# interface.net
KiCad netlist of a schematic drawn in Altium Designer
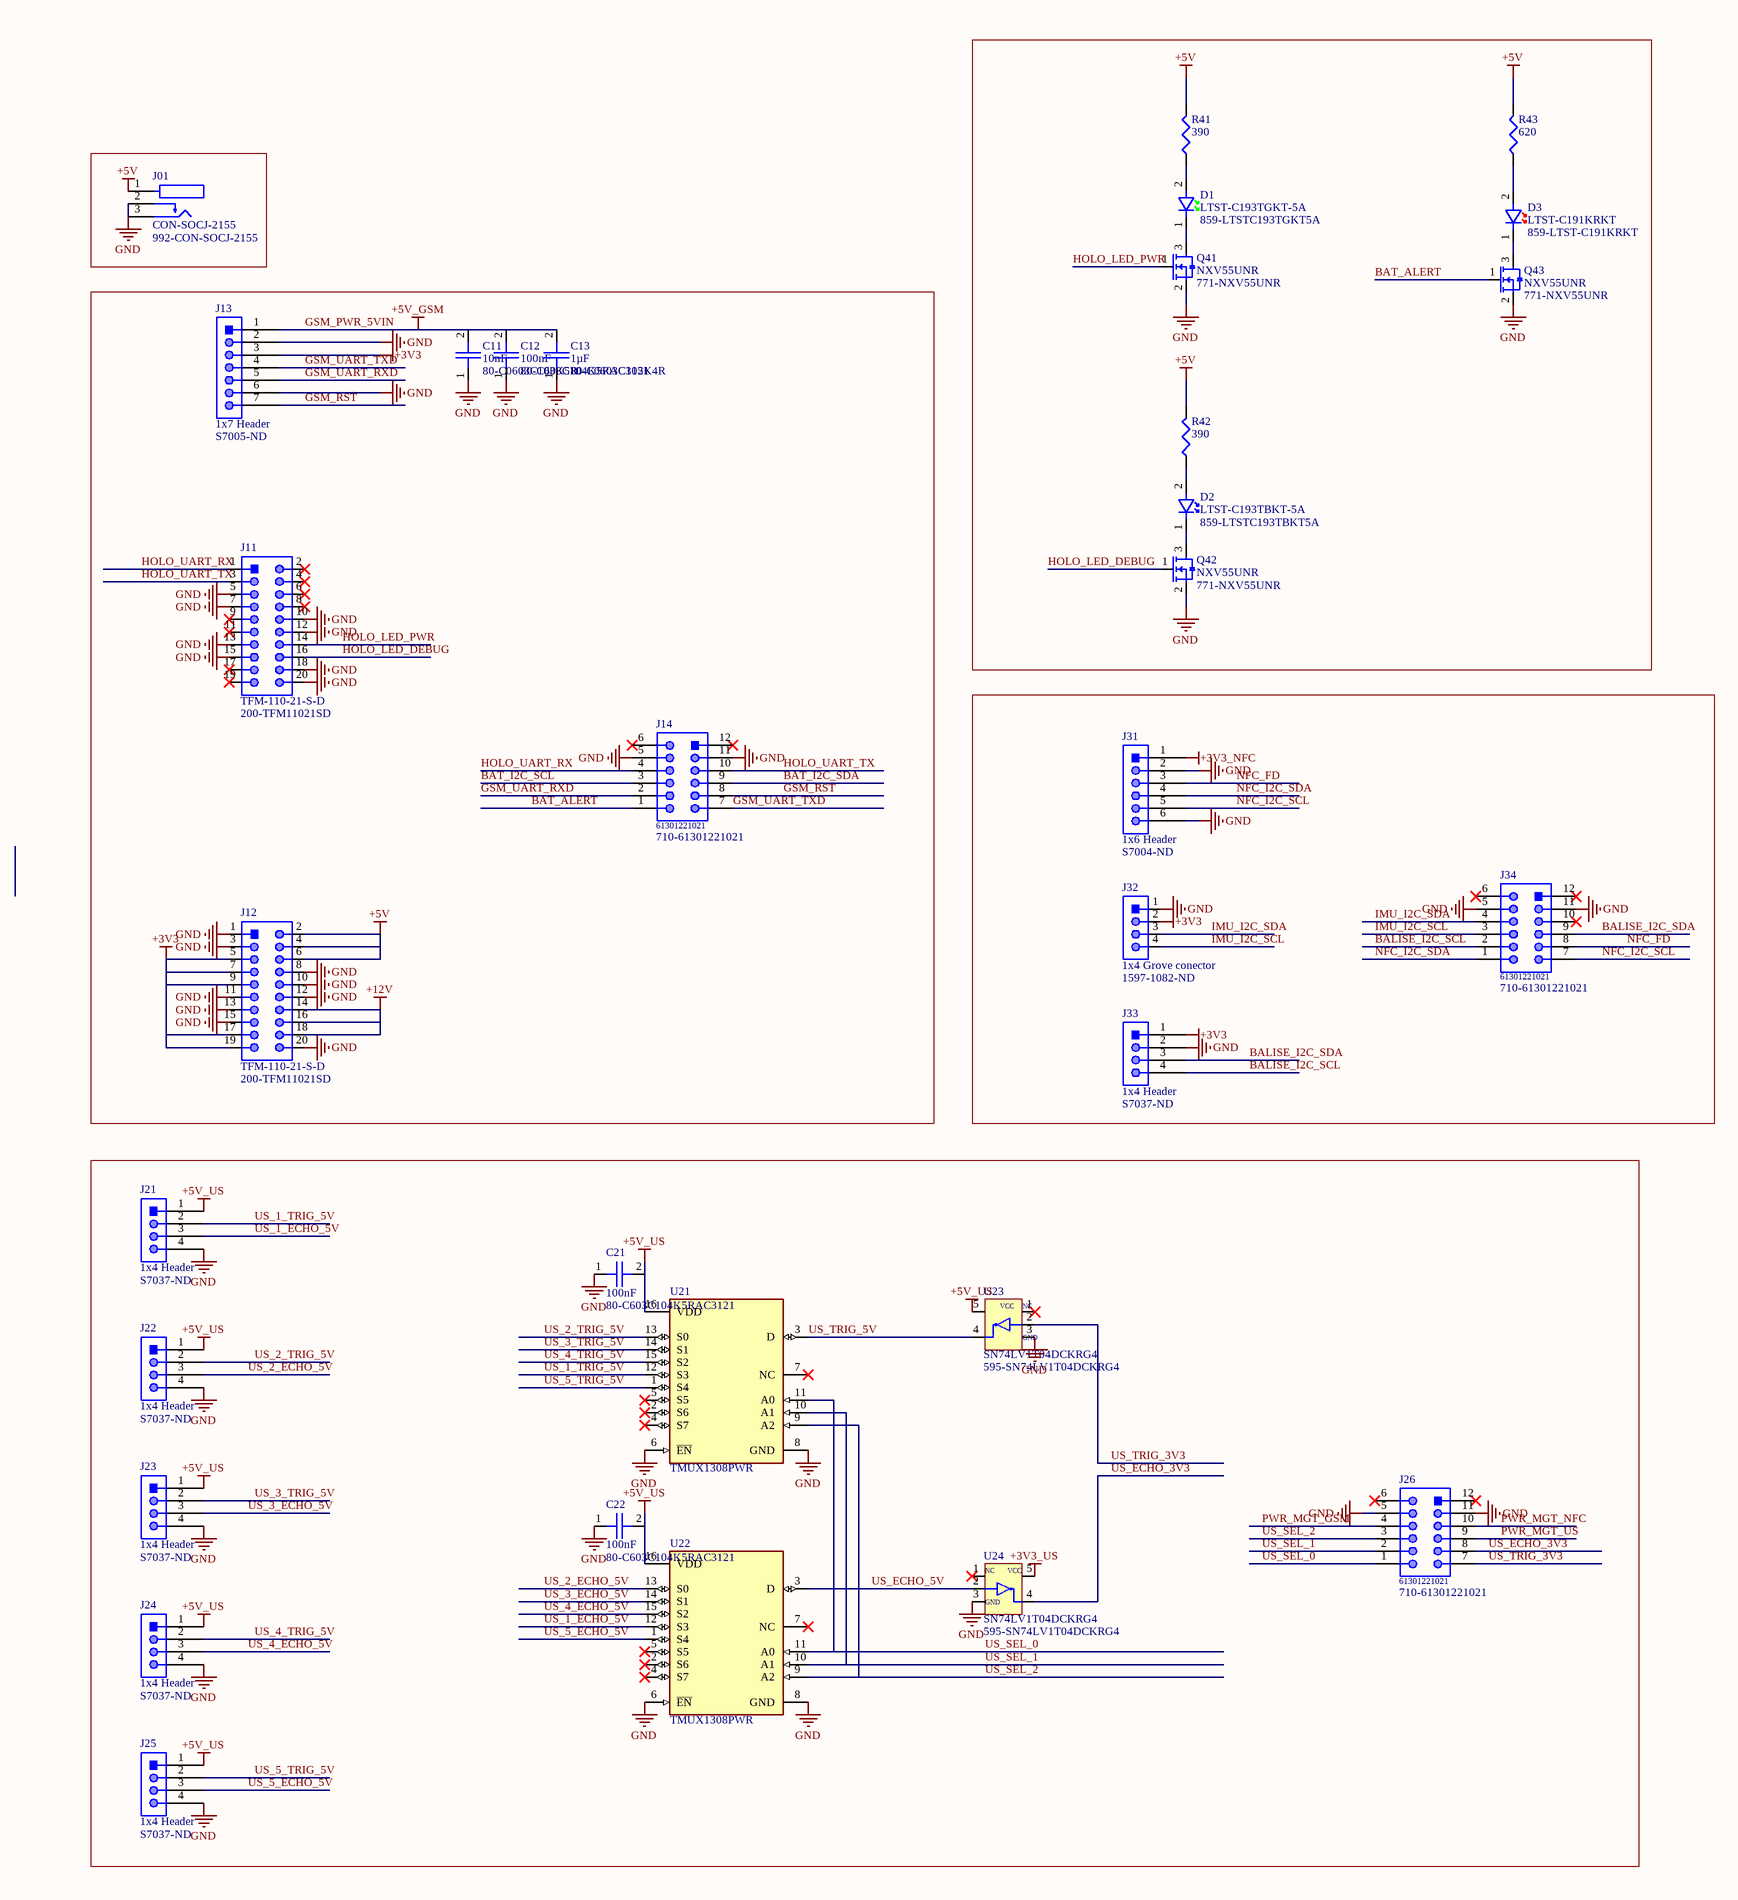
[diagram p0: interface.SchDoc, left]
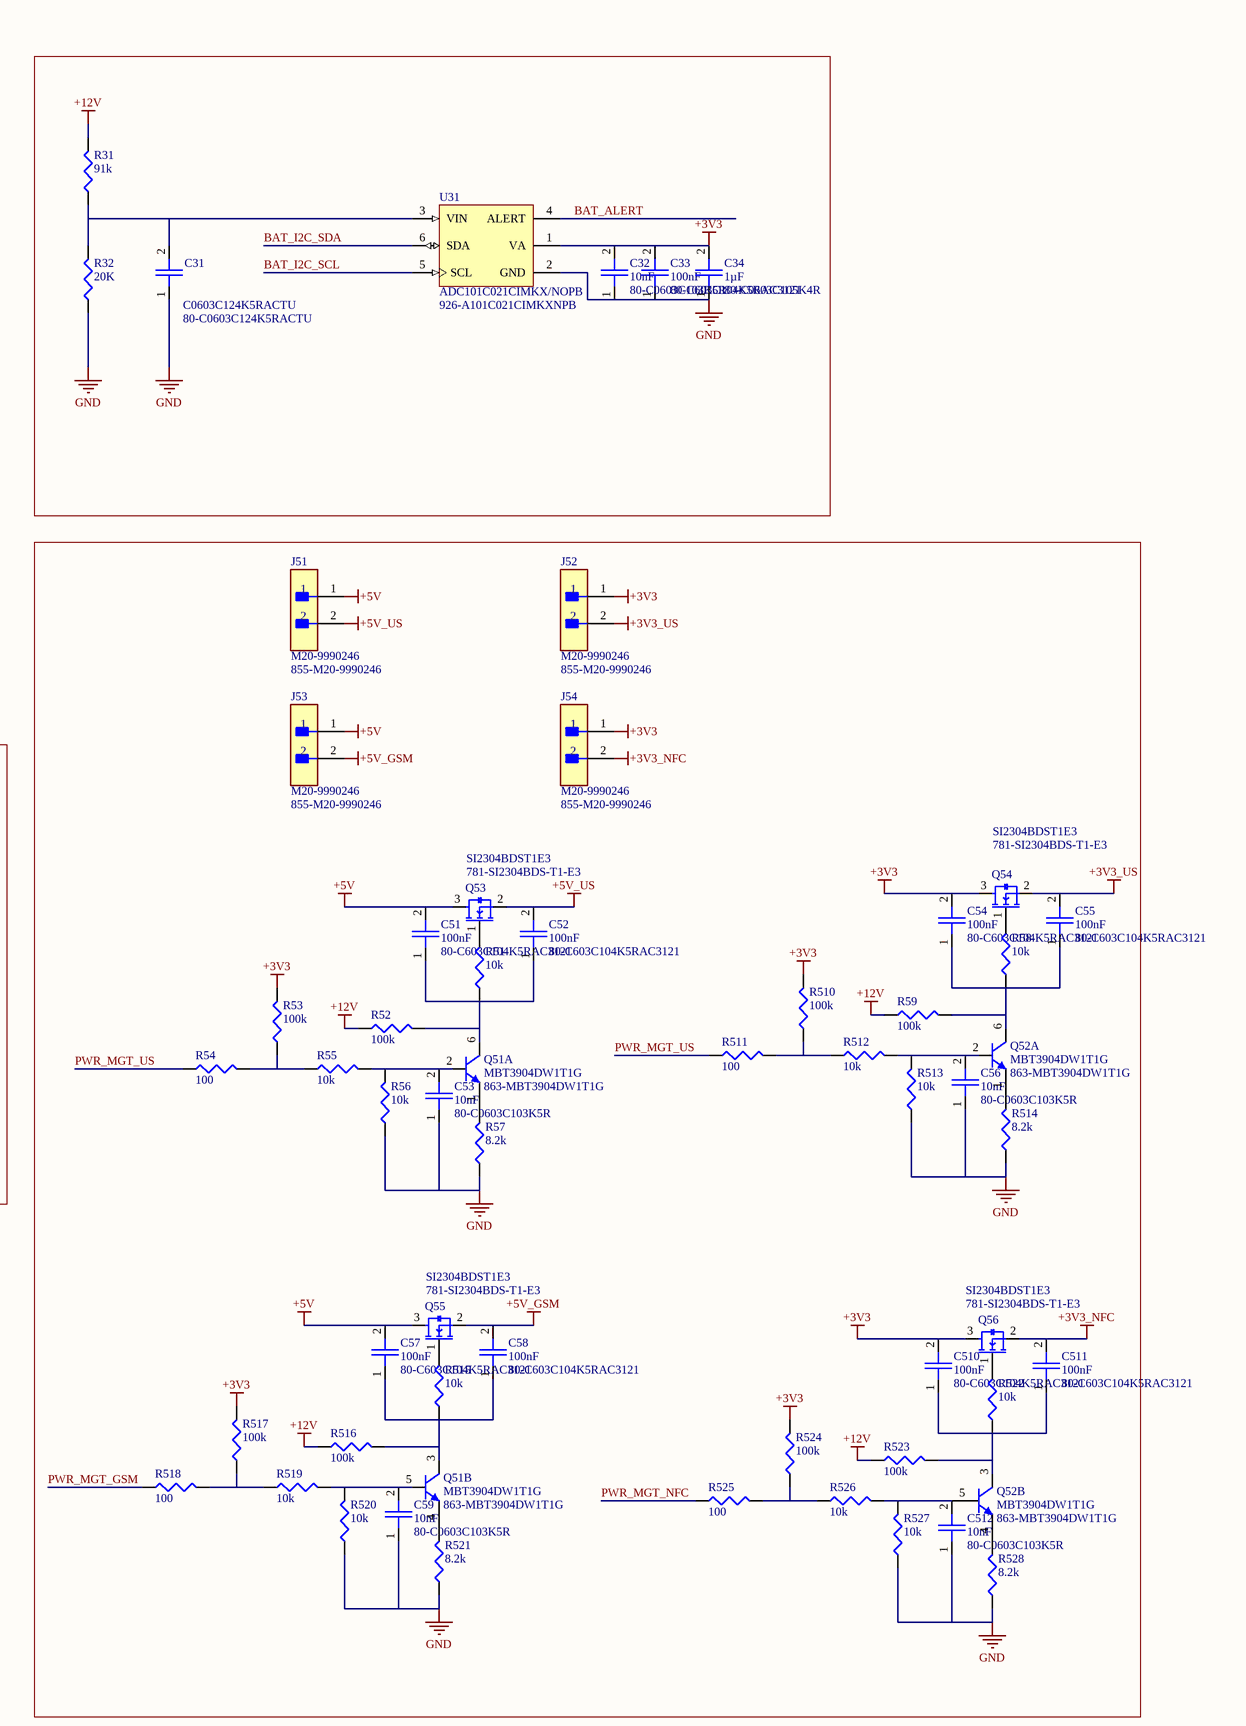
[diagram p1: interface.SchDoc, right]

(export (version "E")
  (design (tool "Eeschema 10.0.6"))
  (components
    (comp (ref "C11")
      (value "10nF")
      (footprint "FP-C0603C-CF-IPC_A")
      (description "CAP CER 10000PF 50V X7R 0603")
      (fields
        (field (name "MANUFACTURER") "KEMET")
        (field (name "MANUFACTURER PART NUMBER") "C0603C103K5RACTU")
        (field (name "SUPPLIER PART NUMBER 1") "80-C0603C103K5R")
      )
      (libsource (lib "interface_Schlib") (part "C0603C103K5RACTU"))
    )
    (comp (ref "C12")
      (value "100nF")
      (footprint "FP-C0603C104K5RAC3121-IPC_A")
      (description "Cap Ceramic 0.1uF 50V X7R 10% Pad SMD 0603 125°C T/R")
      (fields
        (field (name "MANUFACTURER") "KEMET")
        (field (name "MANUFACTURER PART NUMBER") "C0603C104K5RAC3121")
        (field (name "SUPPLIER PART NUMBER 1") "80-C603C104K5RAC3121")
      )
      (libsource (lib "interface_Schlib") (part "C0603C104K5RAC3121"))
    )
    (comp (ref "C13")
      (value "1µF")
      (footprint "CAPC1608X90X35NL15T15")
      (description "Cap Ceramic 1uF 16V X7R 10% SMD 0603 125°C Paper T/R")
      (fields
        (field (name "MANUFACTURER") "KEMET")
        (field (name "MANUFACTURER PART NUMBER") "C0603C105K4RACTU")
        (field (name "SUPPLIER PART NUMBER 1") "80-C0603C105K4R")
      )
      (libsource (lib "interface_Schlib") (part "C0603C105K4RACTU"))
    )
    (comp (ref "C21")
      (value "100nF")
      (footprint "FP-C0603C104K5RAC3121-IPC_A")
      (description "Cap Ceramic 0.1uF 50V X7R 10% Pad SMD 0603 125°C T/R")
      (fields
        (field (name "MANUFACTURER") "KEMET")
        (field (name "MANUFACTURER PART NUMBER") "C0603C104K5RAC3121")
        (field (name "SUPPLIER PART NUMBER 1") "80-C603C104K5RAC3121")
      )
      (libsource (lib "interface_Schlib") (part "C0603C104K5RAC3121"))
    )
    (comp (ref "C22")
      (value "100nF")
      (footprint "FP-C0603C104K5RAC3121-IPC_A")
      (description "Cap Ceramic 0.1uF 50V X7R 10% Pad SMD 0603 125°C T/R")
      (fields
        (field (name "MANUFACTURER") "KEMET")
        (field (name "MANUFACTURER PART NUMBER") "C0603C104K5RAC3121")
        (field (name "SUPPLIER PART NUMBER 1") "80-C603C104K5RAC3121")
      )
      (libsource (lib "interface_Schlib") (part "C0603C104K5RAC3121"))
    )
    (comp (ref "C31")
      (value "C0603C124K5RACTU")
      (footprint "FP-C0603C-CF-IPC_A")
      (description "0603 C 120nF Ceramic Multilayer Capacitor; 50 V; +125degC; X7R Dielec; +/-10%")
      (fields
        (field (name "MANUFACTURER") "KEMET")
        (field (name "TOLERANCE") "10%")
        (field (name "SUPPLIER PART NUMBER 1") "80-C0603C124K5RACTU")
      )
      (libsource (lib "interface_Schlib") (part "C0603C124K5RACTU"))
    )
    (comp (ref "C32")
      (value "10nF")
      (footprint "FP-C0603C-CF-IPC_A")
      (description "CAP CER 10000PF 50V X7R 0603")
      (fields
        (field (name "MANUFACTURER") "KEMET")
        (field (name "MANUFACTURER PART NUMBER") "C0603C103K5RACTU")
        (field (name "SUPPLIER PART NUMBER 1") "80-C0603C103K5R")
      )
      (libsource (lib "interface_Schlib") (part "C0603C103K5RACTU"))
    )
    (comp (ref "C33")
      (value "100nF")
      (footprint "FP-C0603C104K5RAC3121-IPC_A")
      (description "Cap Ceramic 0.1uF 50V X7R 10% Pad SMD 0603 125°C T/R")
      (fields
        (field (name "MANUFACTURER") "KEMET")
        (field (name "MANUFACTURER PART NUMBER") "C0603C104K5RAC3121")
        (field (name "SUPPLIER PART NUMBER 1") "80-C603C104K5RAC3121")
      )
      (libsource (lib "interface_Schlib") (part "C0603C104K5RAC3121"))
    )
    (comp (ref "C34")
      (value "1µF")
      (footprint "CAPC1608X90X35NL15T15")
      (description "Cap Ceramic 1uF 16V X7R 10% SMD 0603 125°C Paper T/R")
      (fields
        (field (name "MANUFACTURER") "KEMET")
        (field (name "MANUFACTURER PART NUMBER") "C0603C105K4RACTU")
        (field (name "SUPPLIER PART NUMBER 1") "80-C0603C105K4R")
      )
      (libsource (lib "interface_Schlib") (part "C0603C105K4RACTU"))
    )
    (comp (ref "C51")
      (value "100nF")
      (footprint "FP-C0603C104K5RAC3121-IPC_A")
      (description "Cap Ceramic 0.1uF 50V X7R 10% Pad SMD 0603 125°C T/R")
      (fields
        (field (name "MANUFACTURER") "KEMET")
        (field (name "MANUFACTURER PART NUMBER") "C0603C104K5RAC3121")
        (field (name "SUPPLIER PART NUMBER 1") "80-C603C104K5RAC3121")
      )
      (libsource (lib "interface_Schlib") (part "C0603C104K5RAC3121"))
    )
    (comp (ref "C52")
      (value "100nF")
      (footprint "FP-C0603C104K5RAC3121-IPC_A")
      (description "Cap Ceramic 0.1uF 50V X7R 10% Pad SMD 0603 125°C T/R")
      (fields
        (field (name "MANUFACTURER") "KEMET")
        (field (name "MANUFACTURER PART NUMBER") "C0603C104K5RAC3121")
        (field (name "SUPPLIER PART NUMBER 1") "80-C603C104K5RAC3121")
      )
      (libsource (lib "interface_Schlib") (part "C0603C104K5RAC3121"))
    )
    (comp (ref "C53")
      (value "10nF")
      (footprint "FP-C0603C-CF-IPC_A")
      (description "CAP CER 10000PF 50V X7R 0603")
      (fields
        (field (name "MANUFACTURER") "KEMET")
        (field (name "MANUFACTURER PART NUMBER") "C0603C103K5RACTU")
        (field (name "SUPPLIER PART NUMBER 1") "80-C0603C103K5R")
      )
      (libsource (lib "interface_Schlib") (part "C0603C103K5RACTU"))
    )
    (comp (ref "C54")
      (value "100nF")
      (footprint "FP-C0603C104K5RAC3121-IPC_A")
      (description "Cap Ceramic 0.1uF 50V X7R 10% Pad SMD 0603 125°C T/R")
      (fields
        (field (name "MANUFACTURER") "KEMET")
        (field (name "MANUFACTURER PART NUMBER") "C0603C104K5RAC3121")
        (field (name "SUPPLIER PART NUMBER 1") "80-C603C104K5RAC3121")
      )
      (libsource (lib "interface_Schlib") (part "C0603C104K5RAC3121"))
    )
    (comp (ref "C55")
      (value "100nF")
      (footprint "FP-C0603C104K5RAC3121-IPC_A")
      (description "Cap Ceramic 0.1uF 50V X7R 10% Pad SMD 0603 125°C T/R")
      (fields
        (field (name "MANUFACTURER") "KEMET")
        (field (name "MANUFACTURER PART NUMBER") "C0603C104K5RAC3121")
        (field (name "SUPPLIER PART NUMBER 1") "80-C603C104K5RAC3121")
      )
      (libsource (lib "interface_Schlib") (part "C0603C104K5RAC3121"))
    )
    (comp (ref "C56")
      (value "10nF")
      (footprint "FP-C0603C-CF-IPC_A")
      (description "CAP CER 10000PF 50V X7R 0603")
      (fields
        (field (name "MANUFACTURER") "KEMET")
        (field (name "MANUFACTURER PART NUMBER") "C0603C103K5RACTU")
        (field (name "SUPPLIER PART NUMBER 1") "80-C0603C103K5R")
      )
      (libsource (lib "interface_Schlib") (part "C0603C103K5RACTU"))
    )
    (comp (ref "C57")
      (value "100nF")
      (footprint "FP-C0603C104K5RAC3121-IPC_A")
      (description "Cap Ceramic 0.1uF 50V X7R 10% Pad SMD 0603 125°C T/R")
      (fields
        (field (name "MANUFACTURER") "KEMET")
        (field (name "MANUFACTURER PART NUMBER") "C0603C104K5RAC3121")
        (field (name "SUPPLIER PART NUMBER 1") "80-C603C104K5RAC3121")
      )
      (libsource (lib "interface_Schlib") (part "C0603C104K5RAC3121"))
    )
    (comp (ref "C58")
      (value "100nF")
      (footprint "FP-C0603C104K5RAC3121-IPC_A")
      (description "Cap Ceramic 0.1uF 50V X7R 10% Pad SMD 0603 125°C T/R")
      (fields
        (field (name "MANUFACTURER") "KEMET")
        (field (name "MANUFACTURER PART NUMBER") "C0603C104K5RAC3121")
        (field (name "SUPPLIER PART NUMBER 1") "80-C603C104K5RAC3121")
      )
      (libsource (lib "interface_Schlib") (part "C0603C104K5RAC3121"))
    )
    (comp (ref "C59")
      (value "10nF")
      (footprint "FP-C0603C-CF-IPC_A")
      (description "CAP CER 10000PF 50V X7R 0603")
      (fields
        (field (name "MANUFACTURER") "KEMET")
        (field (name "MANUFACTURER PART NUMBER") "C0603C103K5RACTU")
        (field (name "SUPPLIER PART NUMBER 1") "80-C0603C103K5R")
      )
      (libsource (lib "interface_Schlib") (part "C0603C103K5RACTU"))
    )
    (comp (ref "C510")
      (value "100nF")
      (footprint "FP-C0603C104K5RAC3121-IPC_A")
      (description "Cap Ceramic 0.1uF 50V X7R 10% Pad SMD 0603 125°C T/R")
      (fields
        (field (name "MANUFACTURER") "KEMET")
        (field (name "MANUFACTURER PART NUMBER") "C0603C104K5RAC3121")
        (field (name "SUPPLIER PART NUMBER 1") "80-C603C104K5RAC3121")
      )
      (libsource (lib "interface_Schlib") (part "C0603C104K5RAC3121"))
    )
    (comp (ref "C511")
      (value "100nF")
      (footprint "FP-C0603C104K5RAC3121-IPC_A")
      (description "Cap Ceramic 0.1uF 50V X7R 10% Pad SMD 0603 125°C T/R")
      (fields
        (field (name "MANUFACTURER") "KEMET")
        (field (name "MANUFACTURER PART NUMBER") "C0603C104K5RAC3121")
        (field (name "SUPPLIER PART NUMBER 1") "80-C603C104K5RAC3121")
      )
      (libsource (lib "interface_Schlib") (part "C0603C104K5RAC3121"))
    )
    (comp (ref "C512")
      (value "10nF")
      (footprint "FP-C0603C-CF-IPC_A")
      (description "CAP CER 10000PF 50V X7R 0603")
      (fields
        (field (name "MANUFACTURER") "KEMET")
        (field (name "MANUFACTURER PART NUMBER") "C0603C103K5RACTU")
        (field (name "SUPPLIER PART NUMBER 1") "80-C0603C103K5R")
      )
      (libsource (lib "interface_Schlib") (part "C0603C103K5RACTU"))
    )
    (comp (ref "D1")
      (value "LTST-C193TGKT-5A")
      (footprint "FP-LTST-C193TGKT-5A")
      (description "0603(H=0.35mm) 绿色 λD=520nm~535nm VR=5V VF=2.5V~3.1V IF=5mA PD=76mW")
      (fields
        (field (name "MANUFACTURER") "Vishay Lite-On")
        (field (name "SUPPLIER PART NUMBER 1") "859-LTSTC193TGKT5A")
      )
      (libsource (lib "interface_Schlib") (part "LTST-C193TGKT-5A"))
    )
    (comp (ref "D2")
      (value "LTST-C193TBKT-5A")
      (footprint "FP-LTST-C193TBKT-5A-MFG")
      (description "0603(H=0.35mm) 蓝色 λD=465nm~475nm VR=5V VF=2.65V~3.05V IF=5mA PD=76mW")
      (fields
        (field (name "MANUFACTURER") "Vishay Lite-On")
        (field (name "SUPPLIER PART NUMBER 1") "859-LTSTC193TBKT5A")
      )
      (libsource (lib "interface_Schlib") (part "LTST-C193TBKT-5A"))
    )
    (comp (ref "D3")
      (value "LTST-C191KRKT")
      (footprint "FP-LTST-C191KRKT")
      (description "0603(H=0.65mm) 红色 λD=631nm VR=5V VF=2.0V~2.4V IF=20mA PD=75mW")
      (fields
        (field (name "MANUFACTURER") "Vishay Lite-On")
        (field (name "SUPPLIER PART NUMBER 1") "859-LTST-C191KRKT")
        (field (name "VOLTAGE") "2V")
      )
      (libsource (lib "interface_Schlib") (part "LTST-C191KRKT"))
    )
    (comp (ref "J01")
      (value "CON-SOCJ-2155")
      (footprint "GRAVITECH_CON-SOCJ-2155")
      (description "DC Power Connectors Power Jack/Connector 2.1mm x 5.5mm")
      (fields
        (field (name "MANUFACTURER") "Gravitech")
        (field (name "SUPPLIER PART NUMBER 1") "992-CON-SOCJ-2155")
      )
      (libsource (lib "interface_Schlib") (part "CON-SOCJ-2155"))
    )
    (comp (ref "J11")
      (value "TFM-110-21-S-D")
      (footprint "SAMTEC_TFM-110-21-S-D")
      (fields (field (name "MANUFACTURER") "Samtec") (field (name "SUPPLIER PART NUMBER 1") "200-TFM11021SD"))
      (libsource (lib "interface_Schlib") (part "TFM-110-21-S-D"))
    )
    (comp (ref "J12")
      (value "TFM-110-21-S-D")
      (footprint "SAMTEC_TFM-110-21-S-D")
      (fields (field (name "MANUFACTURER") "Samtec") (field (name "SUPPLIER PART NUMBER 1") "200-TFM11021SD"))
      (libsource (lib "interface_Schlib") (part "TFM-110-21-S-D"))
    )
    (comp (ref "J13")
      (value "1x7 Header")
      (footprint "header 1x7")
      (description "Female, 7C, Straight, .100\"CC; 3.20mm Tail, No Mt. 100u\" Tin; PBT, Phos Bronze, 105 C")
      (fields
        (field (name "MANUFACTURER") "Sullins")
        (field (name "MANUFACTURER PART NUMBER") "PPTC071LFBN-RC")
        (field (name "SUPPLIER PART NUMBER 1") "S7005-ND")
      )
      (libsource (lib "interface_Schlib") (part "PPTC071LFBN-RC"))
    )
    (comp (ref "J14")
      (value "61301221021")
      (footprint "61301221021")
      (description "THT Angled Pin Header WR-PHD, Pitch 2.54 mm, Dual Row, 12 pins")
      (fields
        (field (name "MANUFACTURER") "Wurth Elektronik")
        (field (name "SUPPLIER PART NUMBER 1") "710-61301221021")
        (field (name "PUBLISHER") "WurthElektronik")
      )
      (libsource (lib "interface_Schlib") (part "61301221021"))
    )
    (comp (ref "J21")
      (value "1x4 Header")
      (footprint "header 1x4")
      (description "4 Positions Embase Connecteur 0,100 po (2,54mm) Trou traversant Or")
      (fields
        (field (name "MANUFACTURER") "Sullins")
        (field (name "MANUFACTURER PART NUMBER") "PPPC041LFBN-RC")
        (field (name "SUPPLIER PART NUMBER 1") "S7037-ND")
      )
      (libsource (lib "interface_Schlib") (part "PPPC041LFBN-RC"))
    )
    (comp (ref "J22")
      (value "1x4 Header")
      (footprint "header 1x4")
      (description "4 Positions Embase Connecteur 0,100 po (2,54mm) Trou traversant Or")
      (fields
        (field (name "MANUFACTURER") "Sullins")
        (field (name "MANUFACTURER PART NUMBER") "PPPC041LFBN-RC")
        (field (name "SUPPLIER PART NUMBER 1") "S7037-ND")
      )
      (libsource (lib "interface_Schlib") (part "PPPC041LFBN-RC"))
    )
    (comp (ref "J23")
      (value "1x4 Header")
      (footprint "header 1x4")
      (description "4 Positions Embase Connecteur 0,100 po (2,54mm) Trou traversant Or")
      (fields
        (field (name "MANUFACTURER") "Sullins")
        (field (name "MANUFACTURER PART NUMBER") "PPPC041LFBN-RC")
        (field (name "SUPPLIER PART NUMBER 1") "S7037-ND")
      )
      (libsource (lib "interface_Schlib") (part "PPPC041LFBN-RC"))
    )
    (comp (ref "J24")
      (value "1x4 Header")
      (footprint "header 1x4")
      (description "4 Positions Embase Connecteur 0,100 po (2,54mm) Trou traversant Or")
      (fields
        (field (name "MANUFACTURER") "Sullins")
        (field (name "MANUFACTURER PART NUMBER") "PPPC041LFBN-RC")
        (field (name "SUPPLIER PART NUMBER 1") "S7037-ND")
      )
      (libsource (lib "interface_Schlib") (part "PPPC041LFBN-RC"))
    )
    (comp (ref "J25")
      (value "1x4 Header")
      (footprint "header 1x4")
      (description "4 Positions Embase Connecteur 0,100 po (2,54mm) Trou traversant Or")
      (fields
        (field (name "MANUFACTURER") "Sullins")
        (field (name "MANUFACTURER PART NUMBER") "PPPC041LFBN-RC")
        (field (name "SUPPLIER PART NUMBER 1") "S7037-ND")
      )
      (libsource (lib "interface_Schlib") (part "PPPC041LFBN-RC"))
    )
    (comp (ref "J26")
      (value "61301221021")
      (footprint "61301221021")
      (description "THT Angled Pin Header WR-PHD, Pitch 2.54 mm, Dual Row, 12 pins")
      (fields
        (field (name "MANUFACTURER") "Wurth Elektronik")
        (field (name "SUPPLIER PART NUMBER 1") "710-61301221021")
        (field (name "PUBLISHER") "WurthElektronik")
      )
      (libsource (lib "interface_Schlib") (part "61301221021"))
    )
    (comp (ref "J31")
      (value "1x6 Header")
      (footprint "header 1x6")
      (description "Female, 6 C, Straight, .100\"CC; 3.20mm Tail, No Mt. 100u\" Tin; PBT, Phos Bronze, 105 C")
      (fields
        (field (name "MANUFACTURER") "Sullins")
        (field (name "MANUFACTURER PART NUMBER") "PPTC061LFBN-RC")
        (field (name "SUPPLIER PART NUMBER 1") "S7004-ND")
      )
      (libsource (lib "interface_Schlib") (part "PPTC061LFBN-RC"))
    )
    (comp (ref "J32")
      (value "1x4 Grove conector")
      (footprint "FP-110990030")
      (description "Grove - Universal 4 pin connector [Seeed Studio] 110990030 Grove - Universal 4 pin connector")
      (fields
        (field (name "MANUFACTURER") "Seeed Studio")
        (field (name "MANUFACTURER PART NUMBER") "110990030")
        (field (name "SUPPLIER PART NUMBER 1") "1597-1082-ND")
      )
      (libsource (lib "interface_Schlib") (part "110990030"))
    )
    (comp (ref "J33")
      (value "1x4 Header")
      (footprint "header 1x4")
      (description "4 Positions Embase Connecteur 0,100 po (2,54mm) Trou traversant Or")
      (fields
        (field (name "MANUFACTURER") "Sullins")
        (field (name "MANUFACTURER PART NUMBER") "PPPC041LFBN-RC")
        (field (name "SUPPLIER PART NUMBER 1") "S7037-ND")
      )
      (libsource (lib "interface_Schlib") (part "PPPC041LFBN-RC"))
    )
    (comp (ref "J34")
      (value "61301221021")
      (footprint "61301221021")
      (description "THT Angled Pin Header WR-PHD, Pitch 2.54 mm, Dual Row, 12 pins")
      (fields
        (field (name "MANUFACTURER") "Wurth Elektronik")
        (field (name "SUPPLIER PART NUMBER 1") "710-61301221021")
        (field (name "PUBLISHER") "WurthElektronik")
      )
      (libsource (lib "interface_Schlib") (part "61301221021"))
    )
    (comp (ref "J51")
      (value "M20-9990246")
      (footprint "FP-M20-9990246-MFG")
      (description "2.54mm (0.1\") Pitch SIL Vertical PC Tail Pin Header, 6.1mm mating pin height, tin, 2 contacts")
      (fields
        (field (name "MANUFACTURER") "Harwin")
        (field (name "SUPPLIER PART NUMBER 1") "855-M20-9990246")
      )
      (libsource (lib "interface_Schlib") (part "M20-9990246"))
    )
    (comp (ref "J52")
      (value "M20-9990246")
      (footprint "FP-M20-9990246-MFG")
      (description "2.54mm (0.1\") Pitch SIL Vertical PC Tail Pin Header, 6.1mm mating pin height, tin, 2 contacts")
      (fields
        (field (name "MANUFACTURER") "Harwin")
        (field (name "SUPPLIER PART NUMBER 1") "855-M20-9990246")
      )
      (libsource (lib "interface_Schlib") (part "M20-9990246"))
    )
    (comp (ref "J53")
      (value "M20-9990246")
      (footprint "FP-M20-9990246-MFG")
      (description "2.54mm (0.1\") Pitch SIL Vertical PC Tail Pin Header, 6.1mm mating pin height, tin, 2 contacts")
      (fields
        (field (name "MANUFACTURER") "Harwin")
        (field (name "SUPPLIER PART NUMBER 1") "855-M20-9990246")
      )
      (libsource (lib "interface_Schlib") (part "M20-9990246"))
    )
    (comp (ref "J54")
      (value "M20-9990246")
      (footprint "FP-M20-9990246-MFG")
      (description "2.54mm (0.1\") Pitch SIL Vertical PC Tail Pin Header, 6.1mm mating pin height, tin, 2 contacts")
      (fields
        (field (name "MANUFACTURER") "Harwin")
        (field (name "SUPPLIER PART NUMBER 1") "855-M20-9990246")
      )
      (libsource (lib "interface_Schlib") (part "M20-9990246"))
    )
    (comp (ref "Q41")
      (value "NXV55UNR")
      (footprint "SOT95P230X110-3N")
      (description "Transistor MOSFET N-Channel 30V 2.3A 3-Pin SOT-23")
      (fields (field (name "MANUFACTURER") "Nexperia") (field (name "SUPPLIER PART NUMBER 1") "771-NXV55UNR"))
      (libsource (lib "interface_Schlib") (part "NXV55UNR"))
    )
    (comp (ref "Q42")
      (value "NXV55UNR")
      (footprint "SOT95P230X110-3N")
      (description "Transistor MOSFET N-Channel 30V 2.3A 3-Pin SOT-23")
      (fields (field (name "MANUFACTURER") "Nexperia") (field (name "SUPPLIER PART NUMBER 1") "771-NXV55UNR"))
      (libsource (lib "interface_Schlib") (part "NXV55UNR"))
    )
    (comp (ref "Q43")
      (value "NXV55UNR")
      (footprint "SOT95P230X110-3N")
      (description "Transistor MOSFET N-Channel 30V 2.3A 3-Pin SOT-23")
      (fields (field (name "MANUFACTURER") "Nexperia") (field (name "SUPPLIER PART NUMBER 1") "771-NXV55UNR"))
      (libsource (lib "interface_Schlib") (part "NXV55UNR"))
    )
    (comp (ref "Q51")
      (value "MBT3904DW1T1G")
      (footprint "ONSC-SOT-363-6-419B-02_W_V")
      (description "Dual General Purpose Transistors, 6-Pin SOT-363, Pb-Free, Tape and Reel")
      (fields
        (field (name "MANUFACTURER") "On Semiconductor")
        (field (name "SUPPLIER PART NUMBER 1") "863-MBT3904DW1T1G")
      )
      (libsource (lib "interface_Schlib") (part "CMP-1048-00877-1"))
    )
    (comp (ref "Q52")
      (value "MBT3904DW1T1G")
      (footprint "ONSC-SOT-363-6-419B-02_W_V")
      (description "Dual General Purpose Transistors, 6-Pin SOT-363, Pb-Free, Tape and Reel")
      (fields
        (field (name "MANUFACTURER") "On Semiconductor")
        (field (name "SUPPLIER PART NUMBER 1") "863-MBT3904DW1T1G")
      )
      (libsource (lib "interface_Schlib") (part "CMP-1048-00877-1"))
    )
    (comp (ref "Q53")
      (value "SI2304BDST1E3")
      (footprint "FP-SI2304BDST1E3")
      (description "Single N-Channel 30 V 0.07 Ohms Surface Mount Power Mosfet - SOT-23")
      (fields
        (field (name "MANUFACTURER") "Vishay")
        (field (name "SUPPLIER PART NUMBER 1") "781-SI2304BDS-T1-E3")
      )
      (libsource (lib "interface_Schlib") (part "SI2304BDST1E3"))
    )
    (comp (ref "Q54")
      (value "SI2304BDST1E3")
      (footprint "FP-SI2304BDST1E3")
      (description "Single N-Channel 30 V 0.07 Ohms Surface Mount Power Mosfet - SOT-23")
      (fields
        (field (name "MANUFACTURER") "Vishay")
        (field (name "SUPPLIER PART NUMBER 1") "781-SI2304BDS-T1-E3")
      )
      (libsource (lib "interface_Schlib") (part "SI2304BDST1E3"))
    )
    (comp (ref "Q55")
      (value "SI2304BDST1E3")
      (footprint "FP-SI2304BDST1E3")
      (description "Single N-Channel 30 V 0.07 Ohms Surface Mount Power Mosfet - SOT-23")
      (fields
        (field (name "MANUFACTURER") "Vishay")
        (field (name "SUPPLIER PART NUMBER 1") "781-SI2304BDS-T1-E3")
      )
      (libsource (lib "interface_Schlib") (part "SI2304BDST1E3"))
    )
    (comp (ref "Q56")
      (value "SI2304BDST1E3")
      (footprint "FP-SI2304BDST1E3")
      (description "Single N-Channel 30 V 0.07 Ohms Surface Mount Power Mosfet - SOT-23")
      (fields
        (field (name "MANUFACTURER") "Vishay")
        (field (name "SUPPLIER PART NUMBER 1") "781-SI2304BDS-T1-E3")
      )
      (libsource (lib "interface_Schlib") (part "SI2304BDST1E3"))
    )
    (comp (ref "R31")
      (value "91k")
      (footprint "RESC2013X50X30ML20T20")
      (libsource (lib "interface_Schlib") (part "resistor"))
    )
    (comp (ref "R32")
      (value "20K")
      (footprint "RESC2013X50X30ML20T20")
      (libsource (lib "interface_Schlib") (part "resistor"))
    )
    (comp (ref "R41")
      (value "390")
      (footprint "RESC2013X50X30ML20T20")
      (libsource (lib "interface_Schlib") (part "resistor"))
    )
    (comp (ref "R42")
      (value "390")
      (footprint "RESC2013X50X30ML20T20")
      (libsource (lib "interface_Schlib") (part "resistor"))
    )
    (comp (ref "R43")
      (value "620")
      (footprint "RESC2013X50X30ML20T20")
      (libsource (lib "interface_Schlib") (part "resistor"))
    )
    (comp (ref "R51")
      (value "10k")
      (footprint "RESC2013X50X30ML20T20")
      (libsource (lib "interface_Schlib") (part "resistor"))
    )
    (comp (ref "R52")
      (value "100k")
      (footprint "RESC2013X50X30ML20T20")
      (libsource (lib "interface_Schlib") (part "resistor"))
    )
    (comp (ref "R53")
      (value "100k")
      (footprint "RESC2013X50X30ML20T20")
      (libsource (lib "interface_Schlib") (part "resistor"))
    )
    (comp (ref "R54")
      (value "100")
      (footprint "RESC2013X50X30ML20T20")
      (libsource (lib "interface_Schlib") (part "resistor"))
    )
    (comp (ref "R55")
      (value "10k")
      (footprint "RESC2013X50X30ML20T20")
      (libsource (lib "interface_Schlib") (part "resistor"))
    )
    (comp (ref "R56")
      (value "10k")
      (footprint "RESC2013X50X30ML20T20")
      (libsource (lib "interface_Schlib") (part "resistor"))
    )
    (comp (ref "R57")
      (value "8.2k")
      (footprint "RESC2013X50X30ML20T20")
      (libsource (lib "interface_Schlib") (part "resistor"))
    )
    (comp (ref "R58")
      (value "10k")
      (footprint "RESC2013X50X30ML20T20")
      (libsource (lib "interface_Schlib") (part "resistor"))
    )
    (comp (ref "R59")
      (value "100k")
      (footprint "RESC2013X50X30ML20T20")
      (libsource (lib "interface_Schlib") (part "resistor"))
    )
    (comp (ref "R510")
      (value "100k")
      (footprint "RESC2013X50X30ML20T20")
      (libsource (lib "interface_Schlib") (part "resistor"))
    )
    (comp (ref "R511")
      (value "100")
      (footprint "RESC2013X50X30ML20T20")
      (libsource (lib "interface_Schlib") (part "resistor"))
    )
    (comp (ref "R512")
      (value "10k")
      (footprint "RESC2013X50X30ML20T20")
      (libsource (lib "interface_Schlib") (part "resistor"))
    )
    (comp (ref "R513")
      (value "10k")
      (footprint "RESC2013X50X30ML20T20")
      (libsource (lib "interface_Schlib") (part "resistor"))
    )
    (comp (ref "R514")
      (value "8.2k")
      (footprint "RESC2013X50X30ML20T20")
      (libsource (lib "interface_Schlib") (part "resistor"))
    )
    (comp (ref "R515")
      (value "10k")
      (footprint "RESC2013X50X30ML20T20")
      (libsource (lib "interface_Schlib") (part "resistor"))
    )
    (comp (ref "R516")
      (value "100k")
      (footprint "RESC2013X50X30ML20T20")
      (libsource (lib "interface_Schlib") (part "resistor"))
    )
    (comp (ref "R517")
      (value "100k")
      (footprint "RESC2013X50X30ML20T20")
      (libsource (lib "interface_Schlib") (part "resistor"))
    )
    (comp (ref "R518")
      (value "100")
      (footprint "RESC2013X50X30ML20T20")
      (libsource (lib "interface_Schlib") (part "resistor"))
    )
    (comp (ref "R519")
      (value "10k")
      (footprint "RESC2013X50X30ML20T20")
      (libsource (lib "interface_Schlib") (part "resistor"))
    )
    (comp (ref "R520")
      (value "10k")
      (footprint "RESC2013X50X30ML20T20")
      (libsource (lib "interface_Schlib") (part "resistor"))
    )
    (comp (ref "R521")
      (value "8.2k")
      (footprint "RESC2013X50X30ML20T20")
      (libsource (lib "interface_Schlib") (part "resistor"))
    )
    (comp (ref "R522")
      (value "10k")
      (footprint "RESC2013X50X30ML20T20")
      (libsource (lib "interface_Schlib") (part "resistor"))
    )
    (comp (ref "R523")
      (value "100k")
      (footprint "RESC2013X50X30ML20T20")
      (libsource (lib "interface_Schlib") (part "resistor"))
    )
    (comp (ref "R524")
      (value "100k")
      (footprint "RESC2013X50X30ML20T20")
      (libsource (lib "interface_Schlib") (part "resistor"))
    )
    (comp (ref "R525")
      (value "100")
      (footprint "RESC2013X50X30ML20T20")
      (libsource (lib "interface_Schlib") (part "resistor"))
    )
    (comp (ref "R526")
      (value "10k")
      (footprint "RESC2013X50X30ML20T20")
      (libsource (lib "interface_Schlib") (part "resistor"))
    )
    (comp (ref "R527")
      (value "10k")
      (footprint "RESC2013X50X30ML20T20")
      (libsource (lib "interface_Schlib") (part "resistor"))
    )
    (comp (ref "R528")
      (value "8.2k")
      (footprint "RESC2013X50X30ML20T20")
      (libsource (lib "interface_Schlib") (part "resistor"))
    )
    (comp (ref "U21")
      (value "TMUX1308PWR")
      (footprint "FP-PW0016A-IPC_A")
      (description "1-CHANNEL, 8:1 GENERAL-PURPOSE A")
      (libsource (lib "interface_Schlib") (part "CMP-04892-000071-1"))
    )
    (comp (ref "U22")
      (value "TMUX1308PWR")
      (footprint "FP-PW0016A-IPC_A")
      (description "1-CHANNEL, 8:1 GENERAL-PURPOSE A")
      (libsource (lib "interface_Schlib") (part "CMP-04892-000071-1"))
    )
    (comp (ref "U23")
      (value "SN74LV1T04DCKRG4")
      (footprint "SOT65P210X110-5N")
      (description "Single Power Supply INVERTER Gate logic level shifter 5-SC70")
      (fields
        (field (name "MANUFACTURER") "Texas Instruments")
        (field (name "SUPPLIER PART NUMBER 1") "595-SN74LV1T04DCKRG4")
      )
      (libsource (lib "interface_Schlib") (part "SN74LV1T04DCKRG4"))
    )
    (comp (ref "U24")
      (value "SN74LV1T04DCKRG4")
      (footprint "SOT65P210X110-5N")
      (description "Single Power Supply INVERTER Gate logic level shifter 5-SC70")
      (fields
        (field (name "MANUFACTURER") "Texas Instruments")
        (field (name "SUPPLIER PART NUMBER 1") "595-SN74LV1T04DCKRG4")
      )
      (libsource (lib "") (part "SN74LV1T04DCKRG4_1"))
    )
    (comp (ref "U31")
      (value "ADC101C021CIMKX/NOPB")
      (footprint "MK06A_N")
      (description "10-Bit, 189kSPS, 1-Ch SAR ADC with I2C and Alert Pin 6-SOT-23-THIN -40 to 105")
      (fields
        (field (name "MANUFACTURER") "TI National Semiconductor")
        (field (name "SUPPLIER PART NUMBER 1") "926-A101C021CIMKXNPB")
      )
      (libsource (lib "interface_Schlib") (part "ADC101C021CIMKX/NOPB"))
    )
  )
  (nets
    (net (code "1") (name "+3V3") (class "Default")
      (node (ref "C32") (pin "2") (pinfunction "2_2") (pintype "passive"))
      (node (ref "C33") (pin "2") (pinfunction "2_2") (pintype "passive"))
      (node (ref "C34") (pin "2") (pinfunction "2_2") (pintype "passive"))
      (node (ref "C510") (pin "2") (pinfunction "2_2") (pintype "passive"))
      (node (ref "C54") (pin "2") (pinfunction "2_2") (pintype "passive"))
      (node (ref "J12") (pin "17") (pinfunction "17_17") (pintype "passive"))
      (node (ref "J12") (pin "19") (pinfunction "19_19") (pintype "passive"))
      (node (ref "J12") (pin "5") (pinfunction "5_5") (pintype "passive"))
      (node (ref "J12") (pin "7") (pinfunction "7_7") (pintype "passive"))
      (node (ref "J12") (pin "9") (pinfunction "9_9") (pintype "passive"))
      (node (ref "J13") (pin "3") (pinfunction "3_3") (pintype "passive"))
      (node (ref "J32") (pin "2") (pinfunction "2_2") (pintype "passive"))
      (node (ref "J33") (pin "1") (pinfunction "1_1") (pintype "passive"))
      (node (ref "J52") (pin "1") (pinfunction "1_1") (pintype "passive"))
      (node (ref "J54") (pin "1") (pinfunction "1_1") (pintype "passive"))
      (node (ref "Q54") (pin "3") (pinfunction "3_3") (pintype "passive"))
      (node (ref "Q56") (pin "3") (pinfunction "3_3") (pintype "passive"))
      (node (ref "R510") (pin "2") (pinfunction "2_2") (pintype "passive"))
      (node (ref "R517") (pin "2") (pinfunction "2_2") (pintype "passive"))
      (node (ref "R524") (pin "2") (pinfunction "2_2") (pintype "passive"))
      (node (ref "R53") (pin "2") (pinfunction "2_2") (pintype "passive"))
      (node (ref "U31") (pin "1") (pinfunction "VA_1") (pintype "power_in"))
    )
    (net (code "2") (name "+3V3_NFC") (class "Default")
      (node (ref "C511") (pin "2") (pinfunction "2_2") (pintype "passive"))
      (node (ref "J31") (pin "1") (pinfunction "1_1") (pintype "passive"))
      (node (ref "J54") (pin "2") (pinfunction "2_2") (pintype "passive"))
      (node (ref "Q56") (pin "2") (pinfunction "2_2") (pintype "passive"))
    )
    (net (code "3") (name "+3V3_US") (class "Default")
      (node (ref "C55") (pin "2") (pinfunction "2_2") (pintype "passive"))
      (node (ref "J52") (pin "2") (pinfunction "2_2") (pintype "passive"))
      (node (ref "Q54") (pin "2") (pinfunction "2_2") (pintype "passive"))
      (node (ref "U24") (pin "5") (pinfunction "VCC_5") (pintype "passive"))
    )
    (net (code "4") (name "+5V") (class "Default")
      (node (ref "C51") (pin "2") (pinfunction "2_2") (pintype "passive"))
      (node (ref "C57") (pin "2") (pinfunction "2_2") (pintype "passive"))
      (node (ref "J01") (pin "1") (pinfunction "1_1") (pintype "passive"))
      (node (ref "J12") (pin "2") (pinfunction "2_2") (pintype "passive"))
      (node (ref "J12") (pin "4") (pinfunction "4_4") (pintype "passive"))
      (node (ref "J12") (pin "6") (pinfunction "6_6") (pintype "passive"))
      (node (ref "J51") (pin "1") (pinfunction "1_1") (pintype "passive"))
      (node (ref "J53") (pin "1") (pinfunction "1_1") (pintype "passive"))
      (node (ref "Q53") (pin "3") (pinfunction "3_3") (pintype "passive"))
      (node (ref "Q55") (pin "3") (pinfunction "3_3") (pintype "passive"))
      (node (ref "R41") (pin "2") (pinfunction "2_2") (pintype "passive"))
      (node (ref "R42") (pin "2") (pinfunction "2_2") (pintype "passive"))
      (node (ref "R43") (pin "2") (pinfunction "2_2") (pintype "passive"))
    )
    (net (code "5") (name "+5V_GSM") (class "Default")
      (node (ref "C11") (pin "2") (pinfunction "2_2") (pintype "passive"))
      (node (ref "C12") (pin "2") (pinfunction "2_2") (pintype "passive"))
      (node (ref "C13") (pin "2") (pinfunction "2_2") (pintype "passive"))
      (node (ref "C58") (pin "2") (pinfunction "2_2") (pintype "passive"))
      (node (ref "J13") (pin "1") (pinfunction "1_1") (pintype "passive"))
      (node (ref "J53") (pin "2") (pinfunction "2_2") (pintype "passive"))
      (node (ref "Q55") (pin "2") (pinfunction "2_2") (pintype "passive"))
    )
    (net (code "6") (name "+5V_US") (class "Default")
      (node (ref "C21") (pin "2") (pinfunction "2_2") (pintype "passive"))
      (node (ref "C22") (pin "2") (pinfunction "2_2") (pintype "passive"))
      (node (ref "C52") (pin "2") (pinfunction "2_2") (pintype "passive"))
      (node (ref "J21") (pin "1") (pinfunction "1_1") (pintype "passive"))
      (node (ref "J22") (pin "1") (pinfunction "1_1") (pintype "passive"))
      (node (ref "J23") (pin "1") (pinfunction "1_1") (pintype "passive"))
      (node (ref "J24") (pin "1") (pinfunction "1_1") (pintype "passive"))
      (node (ref "J25") (pin "1") (pinfunction "1_1") (pintype "passive"))
      (node (ref "J51") (pin "2") (pinfunction "2_2") (pintype "passive"))
      (node (ref "Q53") (pin "2") (pinfunction "2_2") (pintype "passive"))
      (node (ref "U21") (pin "16") (pinfunction "VDD_16") (pintype "power_in"))
      (node (ref "U22") (pin "16") (pinfunction "VDD_16") (pintype "power_in"))
      (node (ref "U23") (pin "5") (pinfunction "VCC_5") (pintype "passive"))
    )
    (net (code "7") (name "+12V") (class "Default")
      (node (ref "J12") (pin "14") (pinfunction "14_14") (pintype "passive"))
      (node (ref "J12") (pin "16") (pinfunction "16_16") (pintype "passive"))
      (node (ref "J12") (pin "18") (pinfunction "18_18") (pintype "passive"))
      (node (ref "R31") (pin "2") (pinfunction "2_2") (pintype "passive"))
      (node (ref "R516") (pin "1") (pinfunction "1_1") (pintype "passive"))
      (node (ref "R52") (pin "1") (pinfunction "1_1") (pintype "passive"))
      (node (ref "R523") (pin "1") (pinfunction "1_1") (pintype "passive"))
      (node (ref "R59") (pin "1") (pinfunction "1_1") (pintype "passive"))
    )
    (net (code "8") (name "/BALISE_I2C_SCL") (class "Default")
      (node (ref "J33") (pin "4") (pinfunction "4_4") (pintype "passive"))
      (node (ref "J34") (pin "2") (pinfunction "2_2") (pintype "passive"))
    )
    (net (code "9") (name "/BALISE_I2C_SDA") (class "Default")
      (node (ref "J33") (pin "3") (pinfunction "3_3") (pintype "passive"))
      (node (ref "J34") (pin "9") (pinfunction "9_9") (pintype "passive"))
    )
    (net (code "10") (name "/BAT_ALERT") (class "Default")
      (node (ref "J14") (pin "1") (pinfunction "1_1") (pintype "passive"))
      (node (ref "Q43") (pin "1") (pinfunction "1_1") (pintype "passive"))
      (node (ref "U31") (pin "4") (pinfunction "ALERT_4") (pintype "open_collector"))
    )
    (net (code "11") (name "/BAT_I2C_SCL") (class "Default")
      (node (ref "J14") (pin "3") (pinfunction "3_3") (pintype "passive"))
      (node (ref "U31") (pin "5") (pinfunction "SCL_5") (pintype "input"))
    )
    (net (code "12") (name "/BAT_I2C_SDA") (class "Default")
      (node (ref "J14") (pin "9") (pinfunction "9_9") (pintype "passive"))
      (node (ref "U31") (pin "6") (pinfunction "SDA_6") (pintype "bidirectional"))
    )
    (net (code "13") (name "/GSM_RST") (class "Default")
      (node (ref "J13") (pin "7") (pinfunction "7_7") (pintype "passive"))
      (node (ref "J14") (pin "8") (pinfunction "8_8") (pintype "passive"))
    )
    (net (code "14") (name "/GSM_UART_RXD") (class "Default")
      (node (ref "J13") (pin "5") (pinfunction "5_5") (pintype "passive"))
      (node (ref "J14") (pin "2") (pinfunction "2_2") (pintype "passive"))
    )
    (net (code "15") (name "/GSM_UART_TXD") (class "Default")
      (node (ref "J13") (pin "4") (pinfunction "4_4") (pintype "passive"))
      (node (ref "J14") (pin "7") (pinfunction "7_7") (pintype "passive"))
    )
    (net (code "16") (name "/HOLO_LED_DEBUG") (class "Default")
      (node (ref "J11") (pin "16") (pinfunction "16_16") (pintype "passive"))
      (node (ref "Q42") (pin "1") (pinfunction "1_1") (pintype "passive"))
    )
    (net (code "17") (name "/HOLO_LED_PWR") (class "Default")
      (node (ref "J11") (pin "14") (pinfunction "14_14") (pintype "passive"))
      (node (ref "Q41") (pin "1") (pinfunction "1_1") (pintype "passive"))
    )
    (net (code "18") (name "/HOLO_UART_RX") (class "Default")
      (node (ref "J11") (pin "1") (pinfunction "1_1") (pintype "passive"))
      (node (ref "J14") (pin "4") (pinfunction "4_4") (pintype "passive"))
    )
    (net (code "19") (name "/HOLO_UART_TX") (class "Default")
      (node (ref "J11") (pin "3") (pinfunction "3_3") (pintype "passive"))
      (node (ref "J14") (pin "10") (pinfunction "10_10") (pintype "passive"))
    )
    (net (code "20") (name "/IMU_I2C_SCL") (class "Default")
      (node (ref "J32") (pin "4") (pinfunction "4_4") (pintype "passive"))
      (node (ref "J34") (pin "3") (pinfunction "3_3") (pintype "passive"))
    )
    (net (code "21") (name "/IMU_I2C_SDA") (class "Default")
      (node (ref "J32") (pin "3") (pinfunction "3_3") (pintype "passive"))
      (node (ref "J34") (pin "4") (pinfunction "4_4") (pintype "passive"))
    )
    (net (code "22") (name "/NFC_FD") (class "Default")
      (node (ref "J31") (pin "3") (pinfunction "3_3") (pintype "passive"))
      (node (ref "J34") (pin "8") (pinfunction "8_8") (pintype "passive"))
    )
    (net (code "23") (name "/NFC_I2C_SCL") (class "Default")
      (node (ref "J31") (pin "5") (pinfunction "5_5") (pintype "passive"))
      (node (ref "J34") (pin "7") (pinfunction "7_7") (pintype "passive"))
    )
    (net (code "24") (name "/NFC_I2C_SDA") (class "Default")
      (node (ref "J31") (pin "4") (pinfunction "4_4") (pintype "passive"))
      (node (ref "J34") (pin "1") (pinfunction "1_1") (pintype "passive"))
    )
    (net (code "25") (name "/PWR_MGT_GSM") (class "Default")
      (node (ref "J26") (pin "4") (pinfunction "4_4") (pintype "passive"))
      (node (ref "R518") (pin "1") (pinfunction "1_1") (pintype "passive"))
    )
    (net (code "26") (name "/PWR_MGT_NFC") (class "Default")
      (node (ref "J26") (pin "10") (pinfunction "10_10") (pintype "passive"))
      (node (ref "R525") (pin "1") (pinfunction "1_1") (pintype "passive"))
    )
    (net (code "27") (name "/PWR_MGT_US") (class "Default")
      (node (ref "J26") (pin "9") (pinfunction "9_9") (pintype "passive"))
      (node (ref "R511") (pin "1") (pinfunction "1_1") (pintype "passive"))
      (node (ref "R54") (pin "1") (pinfunction "1_1") (pintype "passive"))
    )
    (net (code "28") (name "/US_1_ECHO_5V") (class "Default")
      (node (ref "J21") (pin "3") (pinfunction "3_3") (pintype "passive"))
      (node (ref "U22") (pin "12") (pinfunction "S3_12") (pintype "bidirectional"))
    )
    (net (code "29") (name "/US_1_TRIG_5V") (class "Default")
      (node (ref "J21") (pin "2") (pinfunction "2_2") (pintype "passive"))
      (node (ref "U21") (pin "12") (pinfunction "S3_12") (pintype "bidirectional"))
    )
    (net (code "30") (name "/US_2_ECHO_5V") (class "Default")
      (node (ref "J22") (pin "3") (pinfunction "3_3") (pintype "passive"))
      (node (ref "U22") (pin "13") (pinfunction "S0_13") (pintype "bidirectional"))
    )
    (net (code "31") (name "/US_2_TRIG_5V") (class "Default")
      (node (ref "J22") (pin "2") (pinfunction "2_2") (pintype "passive"))
      (node (ref "U21") (pin "13") (pinfunction "S0_13") (pintype "bidirectional"))
    )
    (net (code "32") (name "/US_3_ECHO_5V") (class "Default")
      (node (ref "J23") (pin "3") (pinfunction "3_3") (pintype "passive"))
      (node (ref "U22") (pin "14") (pinfunction "S1_14") (pintype "bidirectional"))
    )
    (net (code "33") (name "/US_3_TRIG_5V") (class "Default")
      (node (ref "J23") (pin "2") (pinfunction "2_2") (pintype "passive"))
      (node (ref "U21") (pin "14") (pinfunction "S1_14") (pintype "bidirectional"))
    )
    (net (code "34") (name "/US_4_ECHO_5V") (class "Default")
      (node (ref "J24") (pin "3") (pinfunction "3_3") (pintype "passive"))
      (node (ref "U22") (pin "15") (pinfunction "S2_15") (pintype "bidirectional"))
    )
    (net (code "35") (name "/US_4_TRIG_5V") (class "Default")
      (node (ref "J24") (pin "2") (pinfunction "2_2") (pintype "passive"))
      (node (ref "U21") (pin "15") (pinfunction "S2_15") (pintype "bidirectional"))
    )
    (net (code "36") (name "/US_5_ECHO_5V") (class "Default")
      (node (ref "J25") (pin "3") (pinfunction "3_3") (pintype "passive"))
      (node (ref "U22") (pin "1") (pinfunction "S4_1") (pintype "bidirectional"))
    )
    (net (code "37") (name "/US_5_TRIG_5V") (class "Default")
      (node (ref "J25") (pin "2") (pinfunction "2_2") (pintype "passive"))
      (node (ref "U21") (pin "1") (pinfunction "S4_1") (pintype "bidirectional"))
    )
    (net (code "38") (name "/US_ECHO_3V3") (class "Default")
      (node (ref "J26") (pin "8") (pinfunction "8_8") (pintype "passive"))
      (node (ref "U24") (pin "4") (pinfunction "4_4") (pintype "passive"))
    )
    (net (code "39") (name "/US_ECHO_5V") (class "Default")
      (node (ref "U22") (pin "3") (pinfunction "D_3") (pintype "bidirectional"))
      (node (ref "U24") (pin "2") (pinfunction "2_2") (pintype "passive"))
    )
    (net (code "40") (name "/US_SEL_0") (class "Default")
      (node (ref "J26") (pin "1") (pinfunction "1_1") (pintype "passive"))
      (node (ref "U21") (pin "11") (pinfunction "A0_11") (pintype "input"))
      (node (ref "U22") (pin "11") (pinfunction "A0_11") (pintype "input"))
    )
    (net (code "41") (name "/US_SEL_1") (class "Default")
      (node (ref "J26") (pin "2") (pinfunction "2_2") (pintype "passive"))
      (node (ref "U21") (pin "10") (pinfunction "A1_10") (pintype "input"))
      (node (ref "U22") (pin "10") (pinfunction "A1_10") (pintype "input"))
    )
    (net (code "42") (name "/US_SEL_2") (class "Default")
      (node (ref "J26") (pin "3") (pinfunction "3_3") (pintype "passive"))
      (node (ref "U21") (pin "9") (pinfunction "A2_9") (pintype "input"))
      (node (ref "U22") (pin "9") (pinfunction "A2_9") (pintype "input"))
    )
    (net (code "43") (name "/US_TRIG_3V3") (class "Default")
      (node (ref "J26") (pin "7") (pinfunction "7_7") (pintype "passive"))
      (node (ref "U23") (pin "2") (pinfunction "2_2") (pintype "passive"))
    )
    (net (code "44") (name "/US_TRIG_5V") (class "Default")
      (node (ref "U21") (pin "3") (pinfunction "D_3") (pintype "bidirectional"))
      (node (ref "U23") (pin "4") (pinfunction "4_4") (pintype "passive"))
    )
    (net (code "45") (name "GND") (class "Default")
      (node (ref "C11") (pin "1") (pinfunction "1_1") (pintype "passive"))
      (node (ref "C12") (pin "1") (pinfunction "1_1") (pintype "passive"))
      (node (ref "C13") (pin "1") (pinfunction "1_1") (pintype "passive"))
      (node (ref "C21") (pin "1") (pinfunction "1_1") (pintype "passive"))
      (node (ref "C22") (pin "1") (pinfunction "1_1") (pintype "passive"))
      (node (ref "C31") (pin "1") (pinfunction "1_1") (pintype "passive"))
      (node (ref "C32") (pin "1") (pinfunction "1_1") (pintype "passive"))
      (node (ref "C33") (pin "1") (pinfunction "1_1") (pintype "passive"))
      (node (ref "C34") (pin "1") (pinfunction "1_1") (pintype "passive"))
      (node (ref "C512") (pin "1") (pinfunction "1_1") (pintype "passive"))
      (node (ref "C53") (pin "1") (pinfunction "1_1") (pintype "passive"))
      (node (ref "C56") (pin "1") (pinfunction "1_1") (pintype "passive"))
      (node (ref "C59") (pin "1") (pinfunction "1_1") (pintype "passive"))
      (node (ref "J01") (pin "2") (pinfunction "2_2") (pintype "passive"))
      (node (ref "J01") (pin "3") (pinfunction "3_3") (pintype "passive"))
      (node (ref "J11") (pin "10") (pinfunction "10_10") (pintype "passive"))
      (node (ref "J11") (pin "12") (pinfunction "12_12") (pintype "passive"))
      (node (ref "J11") (pin "13") (pinfunction "13_13") (pintype "passive"))
      (node (ref "J11") (pin "15") (pinfunction "15_15") (pintype "passive"))
      (node (ref "J11") (pin "18") (pinfunction "18_18") (pintype "passive"))
      (node (ref "J11") (pin "20") (pinfunction "20_20") (pintype "passive"))
      (node (ref "J11") (pin "5") (pinfunction "5_5") (pintype "passive"))
      (node (ref "J11") (pin "7") (pinfunction "7_7") (pintype "passive"))
      (node (ref "J12") (pin "1") (pinfunction "1_1") (pintype "passive"))
      (node (ref "J12") (pin "10") (pinfunction "10_10") (pintype "passive"))
      (node (ref "J12") (pin "11") (pinfunction "11_11") (pintype "passive"))
      (node (ref "J12") (pin "12") (pinfunction "12_12") (pintype "passive"))
      (node (ref "J12") (pin "13") (pinfunction "13_13") (pintype "passive"))
      (node (ref "J12") (pin "15") (pinfunction "15_15") (pintype "passive"))
      (node (ref "J12") (pin "20") (pinfunction "20_20") (pintype "passive"))
      (node (ref "J12") (pin "3") (pinfunction "3_3") (pintype "passive"))
      (node (ref "J12") (pin "8") (pinfunction "8_8") (pintype "passive"))
      (node (ref "J13") (pin "2") (pinfunction "2_2") (pintype "passive"))
      (node (ref "J13") (pin "6") (pinfunction "6_6") (pintype "passive"))
      (node (ref "J14") (pin "11") (pinfunction "11_11") (pintype "passive"))
      (node (ref "J14") (pin "5") (pinfunction "5_5") (pintype "passive"))
      (node (ref "J21") (pin "4") (pinfunction "4_4") (pintype "passive"))
      (node (ref "J22") (pin "4") (pinfunction "4_4") (pintype "passive"))
      (node (ref "J23") (pin "4") (pinfunction "4_4") (pintype "passive"))
      (node (ref "J24") (pin "4") (pinfunction "4_4") (pintype "passive"))
      (node (ref "J25") (pin "4") (pinfunction "4_4") (pintype "passive"))
      (node (ref "J26") (pin "11") (pinfunction "11_11") (pintype "passive"))
      (node (ref "J26") (pin "5") (pinfunction "5_5") (pintype "passive"))
      (node (ref "J31") (pin "2") (pinfunction "2_2") (pintype "passive"))
      (node (ref "J31") (pin "6") (pinfunction "6_6") (pintype "passive"))
      (node (ref "J32") (pin "1") (pinfunction "1_1") (pintype "passive"))
      (node (ref "J33") (pin "2") (pinfunction "2_2") (pintype "passive"))
      (node (ref "J34") (pin "11") (pinfunction "11_11") (pintype "passive"))
      (node (ref "J34") (pin "5") (pinfunction "5_5") (pintype "passive"))
      (node (ref "Q41") (pin "2") (pinfunction "2_2") (pintype "passive"))
      (node (ref "Q42") (pin "2") (pinfunction "2_2") (pintype "passive"))
      (node (ref "Q43") (pin "2") (pinfunction "2_2") (pintype "passive"))
      (node (ref "R32") (pin "1") (pinfunction "1_1") (pintype "passive"))
      (node (ref "R513") (pin "1") (pinfunction "1_1") (pintype "passive"))
      (node (ref "R514") (pin "1") (pinfunction "1_1") (pintype "passive"))
      (node (ref "R520") (pin "1") (pinfunction "1_1") (pintype "passive"))
      (node (ref "R521") (pin "1") (pinfunction "1_1") (pintype "passive"))
      (node (ref "R527") (pin "1") (pinfunction "1_1") (pintype "passive"))
      (node (ref "R528") (pin "1") (pinfunction "1_1") (pintype "passive"))
      (node (ref "R56") (pin "1") (pinfunction "1_1") (pintype "passive"))
      (node (ref "R57") (pin "1") (pinfunction "1_1") (pintype "passive"))
      (node (ref "U21") (pin "6") (pinfunction "~{EN}_6") (pintype "input"))
      (node (ref "U21") (pin "8") (pinfunction "GND_8") (pintype "power_in"))
      (node (ref "U22") (pin "6") (pinfunction "~{EN}_6") (pintype "input"))
      (node (ref "U22") (pin "8") (pinfunction "GND_8") (pintype "power_in"))
      (node (ref "U23") (pin "3") (pinfunction "GND_3") (pintype "passive"))
      (node (ref "U24") (pin "3") (pinfunction "GND_3") (pintype "passive"))
      (node (ref "U31") (pin "2") (pinfunction "GND_2") (pintype "power_in"))
    )
    (net (code "46") (name "Net-(D1-Pad1)") (class "Default")
      (node (ref "D1") (pin "1") (pinfunction "1_1") (pintype "passive"))
      (node (ref "Q41") (pin "3") (pinfunction "3_3") (pintype "passive"))
    )
    (net (code "47") (name "Net-(D1-Pad2)") (class "Default")
      (node (ref "D1") (pin "2") (pinfunction "2_2") (pintype "passive"))
      (node (ref "R41") (pin "1") (pinfunction "1_1") (pintype "passive"))
    )
    (net (code "48") (name "Net-(D2-Pad1)") (class "Default")
      (node (ref "D2") (pin "1") (pinfunction "1_1") (pintype "passive"))
      (node (ref "Q42") (pin "3") (pinfunction "3_3") (pintype "passive"))
    )
    (net (code "49") (name "Net-(D2-Pad2)") (class "Default")
      (node (ref "D2") (pin "2") (pinfunction "2_2") (pintype "passive"))
      (node (ref "R42") (pin "1") (pinfunction "1_1") (pintype "passive"))
    )
    (net (code "50") (name "Net-(D3-Pad1)") (class "Default")
      (node (ref "D3") (pin "1") (pinfunction "1_1") (pintype "passive"))
      (node (ref "Q43") (pin "3") (pinfunction "3_3") (pintype "passive"))
    )
    (net (code "51") (name "Net-(D3-Pad2)") (class "Default")
      (node (ref "D3") (pin "2") (pinfunction "2_2") (pintype "passive"))
      (node (ref "R43") (pin "1") (pinfunction "1_1") (pintype "passive"))
    )
    (net (code "52") (name "Net-(Q51A-B)") (class "Default")
      (node (ref "C53") (pin "2") (pinfunction "2_2") (pintype "passive"))
      (node (ref "Q51") (pin "2") (pinfunction "B_2") (pintype "passive"))
      (node (ref "R55") (pin "2") (pinfunction "2_2") (pintype "passive"))
      (node (ref "R56") (pin "2") (pinfunction "2_2") (pintype "passive"))
    )
    (net (code "53") (name "Net-(Q51A-C)") (class "Default")
      (node (ref "C51") (pin "1") (pinfunction "1_1") (pintype "passive"))
      (node (ref "C52") (pin "1") (pinfunction "1_1") (pintype "passive"))
      (node (ref "Q51") (pin "6") (pinfunction "C_6") (pintype "passive"))
      (node (ref "R51") (pin "1") (pinfunction "1_1") (pintype "passive"))
      (node (ref "R52") (pin "2") (pinfunction "2_2") (pintype "passive"))
    )
    (net (code "54") (name "Net-(Q51A-E)") (class "Default")
      (node (ref "Q51") (pin "1") (pinfunction "E_1") (pintype "passive"))
      (node (ref "R57") (pin "2") (pinfunction "2_2") (pintype "passive"))
    )
    (net (code "55") (name "Net-(Q51B-B)") (class "Default")
      (node (ref "C59") (pin "2") (pinfunction "2_2") (pintype "passive"))
      (node (ref "Q51") (pin "5") (pinfunction "B_5") (pintype "passive"))
      (node (ref "R519") (pin "2") (pinfunction "2_2") (pintype "passive"))
      (node (ref "R520") (pin "2") (pinfunction "2_2") (pintype "passive"))
    )
    (net (code "56") (name "Net-(Q51B-C)") (class "Default")
      (node (ref "C57") (pin "1") (pinfunction "1_1") (pintype "passive"))
      (node (ref "C58") (pin "1") (pinfunction "1_1") (pintype "passive"))
      (node (ref "Q51") (pin "3") (pinfunction "C_3") (pintype "passive"))
      (node (ref "R515") (pin "1") (pinfunction "1_1") (pintype "passive"))
      (node (ref "R516") (pin "2") (pinfunction "2_2") (pintype "passive"))
    )
    (net (code "57") (name "Net-(Q51B-E)") (class "Default")
      (node (ref "Q51") (pin "4") (pinfunction "E_4") (pintype "passive"))
      (node (ref "R521") (pin "2") (pinfunction "2_2") (pintype "passive"))
    )
    (net (code "58") (name "Net-(Q52A-B)") (class "Default")
      (node (ref "C56") (pin "2") (pinfunction "2_2") (pintype "passive"))
      (node (ref "Q52") (pin "2") (pinfunction "B_2") (pintype "passive"))
      (node (ref "R512") (pin "2") (pinfunction "2_2") (pintype "passive"))
      (node (ref "R513") (pin "2") (pinfunction "2_2") (pintype "passive"))
    )
    (net (code "59") (name "Net-(Q52A-C)") (class "Default")
      (node (ref "C54") (pin "1") (pinfunction "1_1") (pintype "passive"))
      (node (ref "C55") (pin "1") (pinfunction "1_1") (pintype "passive"))
      (node (ref "Q52") (pin "6") (pinfunction "C_6") (pintype "passive"))
      (node (ref "R58") (pin "1") (pinfunction "1_1") (pintype "passive"))
      (node (ref "R59") (pin "2") (pinfunction "2_2") (pintype "passive"))
    )
    (net (code "60") (name "Net-(Q52A-E)") (class "Default")
      (node (ref "Q52") (pin "1") (pinfunction "E_1") (pintype "passive"))
      (node (ref "R514") (pin "2") (pinfunction "2_2") (pintype "passive"))
    )
    (net (code "61") (name "Net-(Q52B-B)") (class "Default")
      (node (ref "C512") (pin "2") (pinfunction "2_2") (pintype "passive"))
      (node (ref "Q52") (pin "5") (pinfunction "B_5") (pintype "passive"))
      (node (ref "R526") (pin "2") (pinfunction "2_2") (pintype "passive"))
      (node (ref "R527") (pin "2") (pinfunction "2_2") (pintype "passive"))
    )
    (net (code "62") (name "Net-(Q52B-C)") (class "Default")
      (node (ref "C510") (pin "1") (pinfunction "1_1") (pintype "passive"))
      (node (ref "C511") (pin "1") (pinfunction "1_1") (pintype "passive"))
      (node (ref "Q52") (pin "3") (pinfunction "C_3") (pintype "passive"))
      (node (ref "R522") (pin "1") (pinfunction "1_1") (pintype "passive"))
      (node (ref "R523") (pin "2") (pinfunction "2_2") (pintype "passive"))
    )
    (net (code "63") (name "Net-(Q52B-E)") (class "Default")
      (node (ref "Q52") (pin "4") (pinfunction "E_4") (pintype "passive"))
      (node (ref "R528") (pin "2") (pinfunction "2_2") (pintype "passive"))
    )
    (net (code "64") (name "Net-(Q53-Pad1)") (class "Default")
      (node (ref "Q53") (pin "1") (pinfunction "1_1") (pintype "passive"))
      (node (ref "R51") (pin "2") (pinfunction "2_2") (pintype "passive"))
    )
    (net (code "65") (name "Net-(Q54-Pad1)") (class "Default")
      (node (ref "Q54") (pin "1") (pinfunction "1_1") (pintype "passive"))
      (node (ref "R58") (pin "2") (pinfunction "2_2") (pintype "passive"))
    )
    (net (code "66") (name "Net-(Q55-Pad1)") (class "Default")
      (node (ref "Q55") (pin "1") (pinfunction "1_1") (pintype "passive"))
      (node (ref "R515") (pin "2") (pinfunction "2_2") (pintype "passive"))
    )
    (net (code "67") (name "Net-(Q56-Pad1)") (class "Default")
      (node (ref "Q56") (pin "1") (pinfunction "1_1") (pintype "passive"))
      (node (ref "R522") (pin "2") (pinfunction "2_2") (pintype "passive"))
    )
    (net (code "68") (name "Net-(R53-Pad1)") (class "Default")
      (node (ref "R53") (pin "1") (pinfunction "1_1") (pintype "passive"))
      (node (ref "R54") (pin "2") (pinfunction "2_2") (pintype "passive"))
      (node (ref "R55") (pin "1") (pinfunction "1_1") (pintype "passive"))
    )
    (net (code "69") (name "Net-(R510-Pad1)") (class "Default")
      (node (ref "R510") (pin "1") (pinfunction "1_1") (pintype "passive"))
      (node (ref "R511") (pin "2") (pinfunction "2_2") (pintype "passive"))
      (node (ref "R512") (pin "1") (pinfunction "1_1") (pintype "passive"))
    )
    (net (code "70") (name "Net-(R517-Pad1)") (class "Default")
      (node (ref "R517") (pin "1") (pinfunction "1_1") (pintype "passive"))
      (node (ref "R518") (pin "2") (pinfunction "2_2") (pintype "passive"))
      (node (ref "R519") (pin "1") (pinfunction "1_1") (pintype "passive"))
    )
    (net (code "71") (name "Net-(R524-Pad1)") (class "Default")
      (node (ref "R524") (pin "1") (pinfunction "1_1") (pintype "passive"))
      (node (ref "R525") (pin "2") (pinfunction "2_2") (pintype "passive"))
      (node (ref "R526") (pin "1") (pinfunction "1_1") (pintype "passive"))
    )
    (net (code "72") (name "Net-(U31-VIN)") (class "Default")
      (node (ref "C31") (pin "2") (pinfunction "2_2") (pintype "passive"))
      (node (ref "R31") (pin "1") (pinfunction "1_1") (pintype "passive"))
      (node (ref "R32") (pin "2") (pinfunction "2_2") (pintype "passive"))
      (node (ref "U31") (pin "3") (pinfunction "VIN_3") (pintype "input"))
    )
    (net (code "73") (name "unconnected-(J11-Pad2)") (class "Default")
      (node (ref "J11") (pin "2") (pinfunction "2_2") (pintype "passive+no_connect"))
    )
    (net (code "74") (name "unconnected-(J11-Pad4)") (class "Default")
      (node (ref "J11") (pin "4") (pinfunction "4_4") (pintype "passive+no_connect"))
    )
    (net (code "75") (name "unconnected-(J11-Pad6)") (class "Default")
      (node (ref "J11") (pin "6") (pinfunction "6_6") (pintype "passive+no_connect"))
    )
    (net (code "76") (name "unconnected-(J11-Pad8)") (class "Default")
      (node (ref "J11") (pin "8") (pinfunction "8_8") (pintype "passive+no_connect"))
    )
    (net (code "77") (name "unconnected-(J11-Pad9)") (class "Default")
      (node (ref "J11") (pin "9") (pinfunction "9_9") (pintype "passive+no_connect"))
    )
    (net (code "78") (name "unconnected-(J11-Pad11)") (class "Default")
      (node (ref "J11") (pin "11") (pinfunction "11_11") (pintype "passive+no_connect"))
    )
    (net (code "79") (name "unconnected-(J11-Pad17)") (class "Default")
      (node (ref "J11") (pin "17") (pinfunction "17_17") (pintype "passive+no_connect"))
    )
    (net (code "80") (name "unconnected-(J11-Pad19)") (class "Default")
      (node (ref "J11") (pin "19") (pinfunction "19_19") (pintype "passive+no_connect"))
    )
    (net (code "81") (name "unconnected-(J14-Pad6)") (class "Default")
      (node (ref "J14") (pin "6") (pinfunction "6_6") (pintype "passive+no_connect"))
    )
    (net (code "82") (name "unconnected-(J14-Pad12)") (class "Default")
      (node (ref "J14") (pin "12") (pinfunction "12_12") (pintype "passive+no_connect"))
    )
    (net (code "83") (name "unconnected-(J26-Pad6)") (class "Default")
      (node (ref "J26") (pin "6") (pinfunction "6_6") (pintype "passive+no_connect"))
    )
    (net (code "84") (name "unconnected-(J26-Pad12)") (class "Default")
      (node (ref "J26") (pin "12") (pinfunction "12_12") (pintype "passive+no_connect"))
    )
    (net (code "85") (name "unconnected-(J34-Pad6)") (class "Default")
      (node (ref "J34") (pin "6") (pinfunction "6_6") (pintype "passive+no_connect"))
    )
    (net (code "86") (name "unconnected-(J34-Pad10)") (class "Default")
      (node (ref "J34") (pin "10") (pinfunction "10_10") (pintype "passive+no_connect"))
    )
    (net (code "87") (name "unconnected-(J34-Pad12)") (class "Default")
      (node (ref "J34") (pin "12") (pinfunction "12_12") (pintype "passive+no_connect"))
    )
    (net (code "88") (name "unconnected-(U21-NC-Pad7)") (class "Default")
      (node (ref "U21") (pin "7") (pinfunction "NC_7") (pintype "power_in+no_connect"))
    )
    (net (code "89") (name "unconnected-(U21-S5-Pad5)") (class "Default")
      (node (ref "U21") (pin "5") (pinfunction "S5_5") (pintype "bidirectional+no_connect"))
    )
    (net (code "90") (name "unconnected-(U21-S6-Pad2)") (class "Default")
      (node (ref "U21") (pin "2") (pinfunction "S6_2") (pintype "bidirectional+no_connect"))
    )
    (net (code "91") (name "unconnected-(U21-S7-Pad4)") (class "Default")
      (node (ref "U21") (pin "4") (pinfunction "S7_4") (pintype "bidirectional+no_connect"))
    )
    (net (code "92") (name "unconnected-(U22-NC-Pad7)") (class "Default")
      (node (ref "U22") (pin "7") (pinfunction "NC_7") (pintype "power_in+no_connect"))
    )
    (net (code "93") (name "unconnected-(U22-S5-Pad5)") (class "Default")
      (node (ref "U22") (pin "5") (pinfunction "S5_5") (pintype "bidirectional+no_connect"))
    )
    (net (code "94") (name "unconnected-(U22-S6-Pad2)") (class "Default")
      (node (ref "U22") (pin "2") (pinfunction "S6_2") (pintype "bidirectional+no_connect"))
    )
    (net (code "95") (name "unconnected-(U22-S7-Pad4)") (class "Default")
      (node (ref "U22") (pin "4") (pinfunction "S7_4") (pintype "bidirectional+no_connect"))
    )
    (net (code "96") (name "unconnected-(U23-NC-Pad1)") (class "Default")
      (node (ref "U23") (pin "1") (pinfunction "NC_1") (pintype "passive+no_connect"))
    )
    (net (code "97") (name "unconnected-(U24-NC-Pad1)") (class "Default")
      (node (ref "U24") (pin "1") (pinfunction "NC_1") (pintype "passive+no_connect"))
    )
  )
)
